# Adafruit_nRF52_Bluefruit_Feather_rev_G.net
KiCad netlist of a schematic drawn in EAGLE
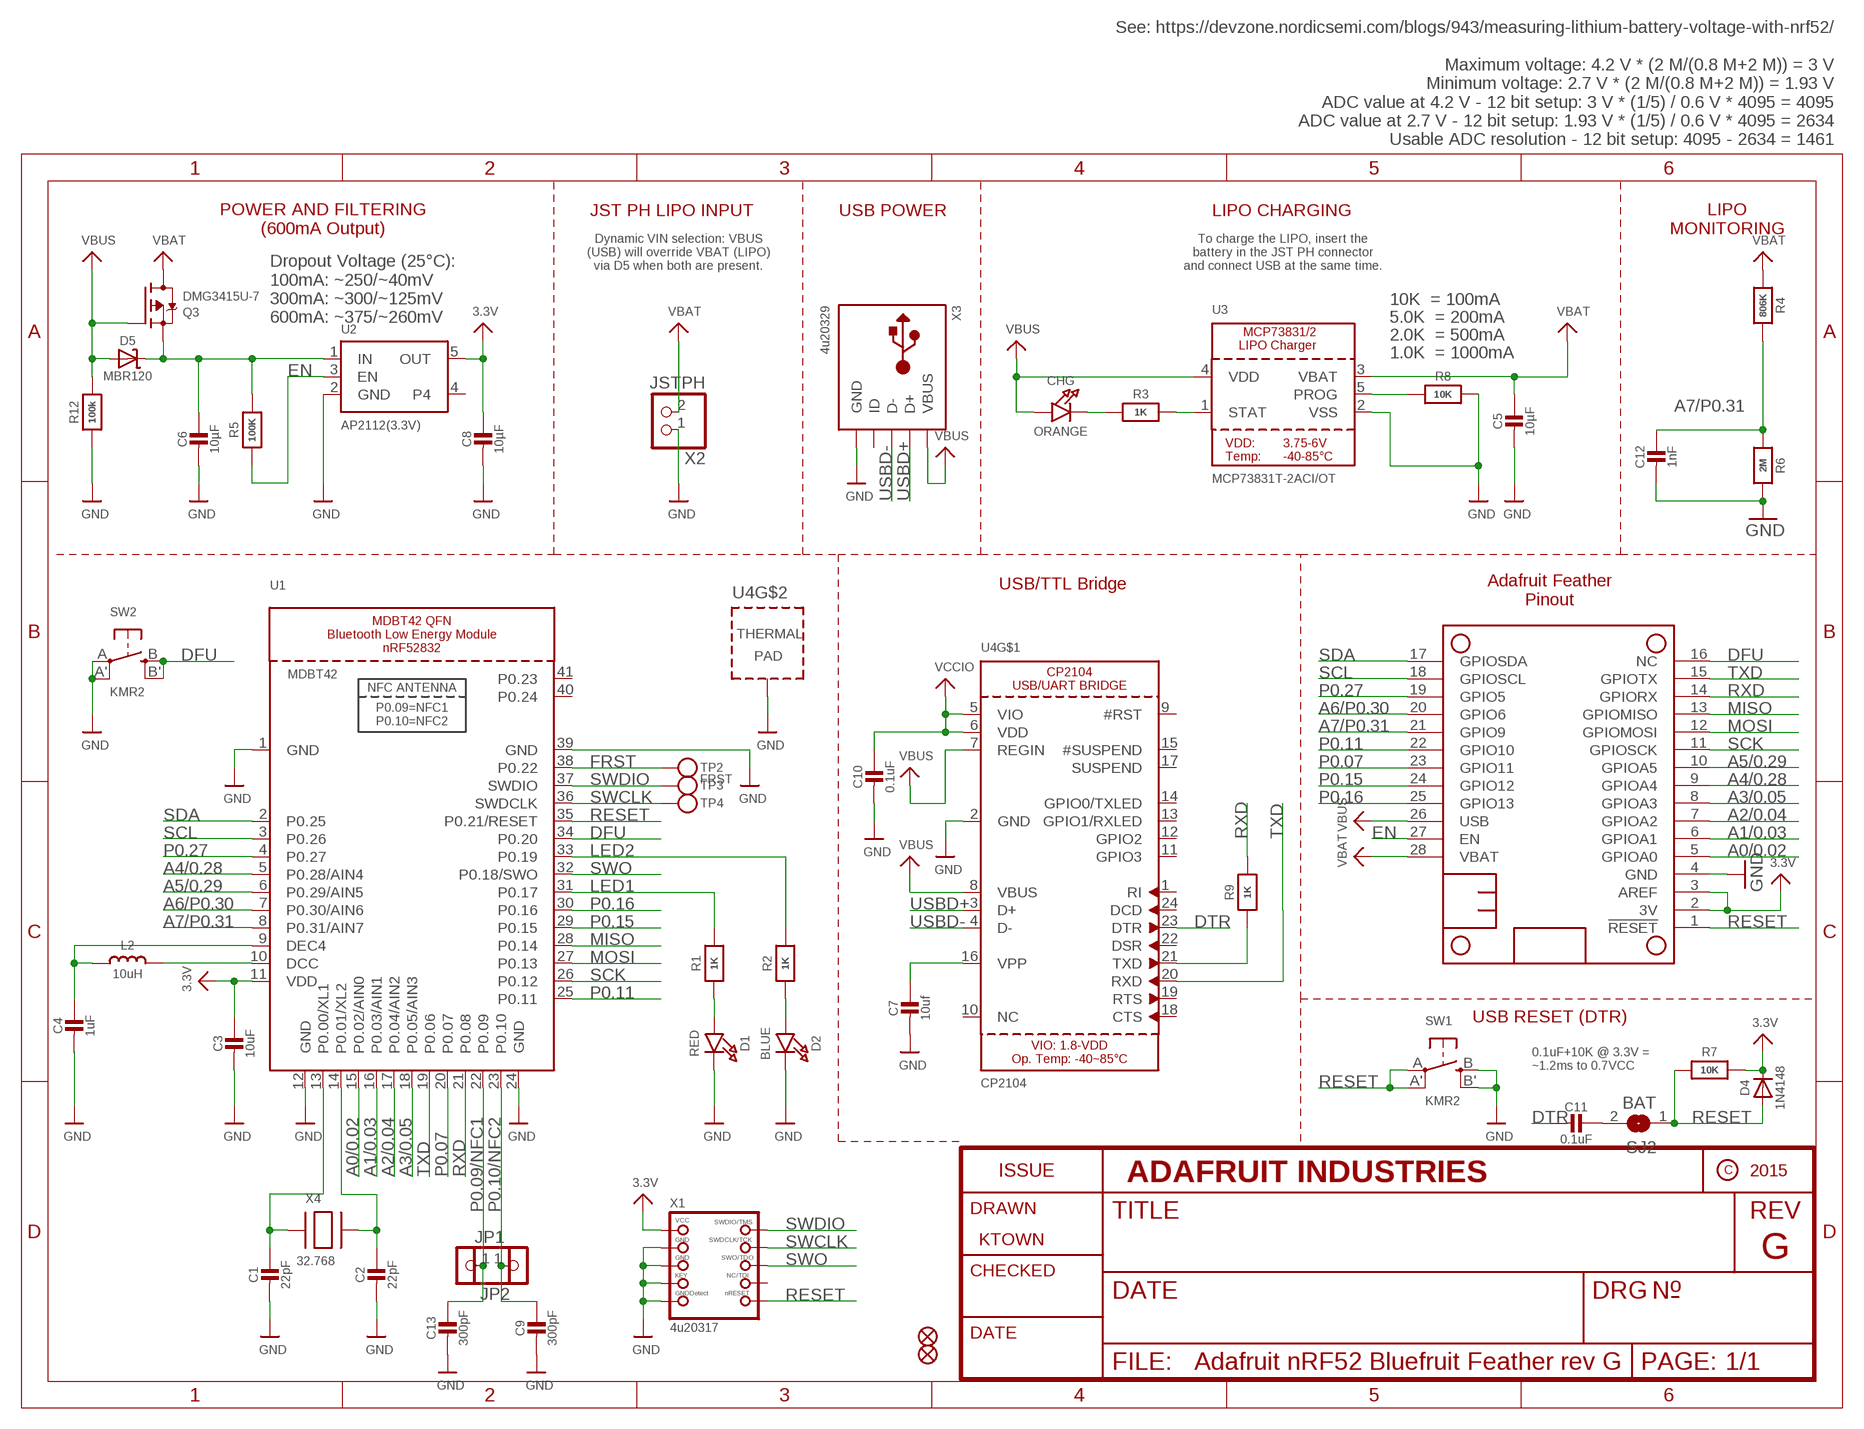
[diagram p0: schematic, sheet 1]

(export (version "E")
  (design (tool "Eeschema 10.0.6"))
  (components
    (comp (ref "C1")
      (value "22pF")
      (footprint "eagle-import:0603-NO")
      (libsource (lib "eagle-import") (part "CAP_CERAMIC0603_NO"))
    )
    (comp (ref "C2")
      (value "22pF")
      (footprint "eagle-import:0603-NO")
      (libsource (lib "eagle-import") (part "CAP_CERAMIC0603_NO"))
    )
    (comp (ref "C3")
      (value "10uF")
      (footprint "eagle-import:0805-NO")
      (libsource (lib "eagle-import") (part "CAP_CERAMIC0805-NOOUTLINE"))
    )
    (comp (ref "C4")
      (value "1uF")
      (footprint "eagle-import:0603-NO")
      (libsource (lib "eagle-import") (part "CAP_CERAMIC0603_NO"))
    )
    (comp (ref "C5")
      (value "10µF")
      (footprint "eagle-import:0805-NO")
      (libsource (lib "eagle-import") (part "CAP_CERAMIC0805-NOOUTLINE"))
    )
    (comp (ref "C6")
      (value "10µF")
      (footprint "eagle-import:0805-NO")
      (libsource (lib "eagle-import") (part "CAP_CERAMIC0805-NOOUTLINE"))
    )
    (comp (ref "C7")
      (value "10uf")
      (footprint "eagle-import:0805-NO")
      (libsource (lib "eagle-import") (part "CAP_CERAMIC0805-NOOUTLINE"))
    )
    (comp (ref "C8")
      (value "10µF")
      (footprint "eagle-import:0805-NO")
      (libsource (lib "eagle-import") (part "CAP_CERAMIC0805-NOOUTLINE"))
    )
    (comp (ref "C9")
      (value "300pF")
      (footprint "eagle-import:_0603MP")
      (libsource (lib "eagle-import") (part "CAP_CERAMIC_0603MP"))
    )
    (comp (ref "C10")
      (value "0.1uF")
      (footprint "eagle-import:0603-NO")
      (libsource (lib "eagle-import") (part "CAP_CERAMIC0603_NO"))
    )
    (comp (ref "C11")
      (value "0.1uF")
      (footprint "eagle-import:0603-NO")
      (libsource (lib "eagle-import") (part "CAP_CERAMIC0603_NO"))
    )
    (comp (ref "C12")
      (value "1nF")
      (footprint "eagle-import:0603-NO")
      (libsource (lib "eagle-import") (part "CAP_CERAMIC0603_NO"))
    )
    (comp (ref "C13")
      (value "300pF")
      (footprint "eagle-import:_0603MP")
      (libsource (lib "eagle-import") (part "CAP_CERAMIC_0603MP"))
    )
    (comp (ref "CHG")
      (value "ORANGE")
      (footprint "eagle-import:CHIPLED_0805_NOOUTLINE")
      (libsource (lib "eagle-import") (part "LED0805_NOOUTLINE"))
    )
    (comp (ref "D1")
      (value "RED")
      (footprint "eagle-import:CHIPLED_0805_NOOUTLINE")
      (libsource (lib "eagle-import") (part "LED0805_NOOUTLINE"))
    )
    (comp (ref "D2")
      (value "BLUE")
      (footprint "eagle-import:CHIPLED_0805_NOOUTLINE")
      (libsource (lib "eagle-import") (part "LED0805_NOOUTLINE"))
    )
    (comp (ref "D4")
      (value "1N4148")
      (footprint "eagle-import:SOD-323")
      (libsource (lib "eagle-import") (part "DIODESOD-323"))
    )
    (comp (ref "D5")
      (value "MBR120")
      (footprint "eagle-import:SOD-123")
      (libsource (lib "eagle-import") (part "DIODE-SCHOTTKYSOD-123"))
    )
    (comp (ref "FID1")
      (value "FIDUCIAL_1MM")
      (footprint "eagle-import:FIDUCIAL_1MM")
      (libsource (lib "eagle-import") (part "FIDUCIAL_1MM"))
    )
    (comp (ref "FID3")
      (value "FIDUCIAL_1MM")
      (footprint "eagle-import:FIDUCIAL_1MM")
      (libsource (lib "eagle-import") (part "FIDUCIAL_1MM"))
    )
    (comp (ref "JP1")
      (value "HEADER-1X12MM")
      (footprint "eagle-import:1X01_2MM")
      (libsource (lib "eagle-import") (part "HEADER-1X12MM"))
    )
    (comp (ref "JP2")
      (value "HEADER-1X12MM")
      (footprint "eagle-import:1X01_2MM")
      (libsource (lib "eagle-import") (part "HEADER-1X12MM"))
    )
    (comp (ref "L2")
      (value "10uH")
      (footprint "eagle-import:0805-NO")
      (libsource (lib "eagle-import") (part "INDUCTOR0805-NO"))
    )
    (comp (ref "MS1")
      (value "FEATHERWING_NODIM")
      (footprint "eagle-import:FEATHERWING_NODIM")
      (libsource (lib "eagle-import") (part "FEATHERWING_NODIM"))
    )
    (comp (ref "Q3")
      (value "DMG3415U-7")
      (footprint "eagle-import:SOT23-R")
      (libsource (lib "eagle-import") (part "MOSFET-P"))
    )
    (comp (ref "R1")
      (value "1K")
      (footprint "eagle-import:0603-NO")
      (libsource (lib "eagle-import") (part "RESISTOR_0603_NOOUT"))
    )
    (comp (ref "R2")
      (value "1K")
      (footprint "eagle-import:0603-NO")
      (libsource (lib "eagle-import") (part "RESISTOR_0603_NOOUT"))
    )
    (comp (ref "R3")
      (value "1K")
      (footprint "eagle-import:0603-NO")
      (libsource (lib "eagle-import") (part "RESISTOR_0603_NOOUT"))
    )
    (comp (ref "R4")
      (value "806K")
      (footprint "eagle-import:0603-NO")
      (libsource (lib "eagle-import") (part "RESISTOR_0603_NOOUT"))
    )
    (comp (ref "R5")
      (value "100K")
      (footprint "eagle-import:0603-NO")
      (libsource (lib "eagle-import") (part "RESISTOR_0603_NOOUT"))
    )
    (comp (ref "R6")
      (value "2M")
      (footprint "eagle-import:0603-NO")
      (libsource (lib "eagle-import") (part "RESISTOR_0603_NOOUT"))
    )
    (comp (ref "R7")
      (value "10K")
      (footprint "eagle-import:0603-NO")
      (libsource (lib "eagle-import") (part "RESISTOR_0603_NOOUT"))
    )
    (comp (ref "R8")
      (value "10K")
      (footprint "eagle-import:0603-NO")
      (libsource (lib "eagle-import") (part "RESISTOR_0603_NOOUT"))
    )
    (comp (ref "R9")
      (value "1K")
      (footprint "eagle-import:0603-NO")
      (libsource (lib "eagle-import") (part "RESISTOR_0603_NOOUT"))
    )
    (comp (ref "R12")
      (value "100k")
      (footprint "eagle-import:0603-NO")
      (libsource (lib "eagle-import") (part "RESISTOR_0603_NOOUT"))
    )
    (comp (ref "SJ2")
      (value "BAT")
      (footprint "eagle-import:SOLDERJUMPER_CLOSEDWIRE")
      (libsource (lib "eagle-import") (part "SOLDERJUMPERCLOSED"))
    )
    (comp (ref "SW1")
      (value "KMR2")
      (footprint "eagle-import:BTN_KMR2_4.6X2.8")
      (libsource (lib "eagle-import") (part "SWITCH_TACT_SMT4.6X2.8"))
    )
    (comp (ref "SW2")
      (value "KMR2")
      (footprint "eagle-import:BTN_KMR2_4.6X2.8")
      (libsource (lib "eagle-import") (part "SWITCH_TACT_SMT4.6X2.8"))
    )
    (comp (ref "TP2")
      (value "FRST")
      (footprint "eagle-import:PAD-1.5X2.0")
      (libsource (lib "eagle-import") (part "TESTPOINT1.5X2.0MM_NOCREAM"))
    )
    (comp (ref "TP3")
      (value "TESTPOINTROUND2MM")
      (footprint "eagle-import:TESTPOINT_ROUND_2MM")
      (libsource (lib "eagle-import") (part "TESTPOINTROUND2MM"))
    )
    (comp (ref "TP4")
      (value "TESTPOINTROUND2MM")
      (footprint "eagle-import:TESTPOINT_ROUND_2MM")
      (libsource (lib "eagle-import") (part "TESTPOINTROUND2MM"))
    )
    (comp (ref "U1")
      (value "MDBT42")
      (footprint "eagle-import:BLE_MODULE_RAYTAC_MDBT42")
      (libsource (lib "eagle-import") (part "NRF52832_MODULE_MDBT42"))
    )
    (comp (ref "U2")
      (value "AP2112(3.3V)")
      (footprint "eagle-import:SOT23-5")
      (libsource (lib "eagle-import") (part "VREG_SOT23-5"))
    )
    (comp (ref "U3")
      (value "MCP73831T-2ACI/OT")
      (footprint "eagle-import:SOT23-5")
      (libsource (lib "eagle-import") (part "MCP73831/2"))
    )
    (comp (ref "U4")
      (value "CP2104")
      (footprint "eagle-import:QFN24_4MM_SMSC")
      (libsource (lib "eagle-import") (part "CP2104"))
    )
    (comp (ref "X1")
      (value "4u20317")
      (footprint "eagle-import:2X05_1.27MM_BOX_POSTS")
      (libsource (lib "eagle-import") (part "JTAG-CORTEXBOXPOSTS"))
    )
    (comp (ref "X2")
      (value "JSTPH")
      (footprint "eagle-import:JSTPH2")
      (libsource (lib "eagle-import") (part "CON_JST_PH_2PIN"))
    )
    (comp (ref "X3")
      (value "4u20329")
      (footprint "eagle-import:4UCONN_20329_V2")
      (libsource (lib "eagle-import") (part "USB_MICRO_20329_V2"))
    )
    (comp (ref "X4")
      (value "32.768")
      (footprint "eagle-import:XTAL3215")
      (libsource (lib "eagle-import") (part "XTAL-3.2X1.5"))
    )
  )
  (nets
    (net (code "1") (name "/A0{slash}0.02") (class "Default")
      (node (ref "MS1") (pin "5") (pinfunction "GPIOA0_5") (pintype "bidirectional"))
      (node (ref "U1") (pin "15") (pinfunction "P0.02/AIN0_15") (pintype "bidirectional"))
    )
    (net (code "2") (name "/A1{slash}0.03") (class "Default")
      (node (ref "MS1") (pin "6") (pinfunction "GPIOA1_6") (pintype "bidirectional"))
      (node (ref "U1") (pin "16") (pinfunction "P0.03/AIN1_16") (pintype "bidirectional"))
    )
    (net (code "3") (name "/A2{slash}0.04") (class "Default")
      (node (ref "MS1") (pin "7") (pinfunction "GPIOA2_7") (pintype "bidirectional"))
      (node (ref "U1") (pin "17") (pinfunction "P0.04/AIN2_17") (pintype "bidirectional"))
    )
    (net (code "4") (name "/A3{slash}0.05") (class "Default")
      (node (ref "MS1") (pin "8") (pinfunction "GPIOA3_8") (pintype "bidirectional"))
      (node (ref "U1") (pin "18") (pinfunction "P0.05/AIN3_18") (pintype "bidirectional"))
    )
    (net (code "5") (name "/A4{slash}0.28") (class "Default")
      (node (ref "MS1") (pin "9") (pinfunction "GPIOA4_9") (pintype "bidirectional"))
      (node (ref "U1") (pin "5") (pinfunction "P0.28/AIN4_5") (pintype "bidirectional"))
    )
    (net (code "6") (name "/A5{slash}0.29") (class "Default")
      (node (ref "MS1") (pin "10") (pinfunction "GPIOA5_10") (pintype "bidirectional"))
      (node (ref "U1") (pin "6") (pinfunction "P0.29/AIN5_6") (pintype "bidirectional"))
    )
    (net (code "7") (name "/A6{slash}P0.30") (class "Default")
      (node (ref "MS1") (pin "20") (pinfunction "GPIO6_20") (pintype "bidirectional"))
      (node (ref "U1") (pin "7") (pinfunction "P0.30/AIN6_7") (pintype "bidirectional"))
    )
    (net (code "8") (name "/A7{slash}P0.31") (class "Default")
      (node (ref "C12") (pin "1") (pinfunction "1_1") (pintype "passive"))
      (node (ref "MS1") (pin "21") (pinfunction "GPIO9_21") (pintype "bidirectional"))
      (node (ref "R4") (pin "2") (pinfunction "2_2") (pintype "passive"))
      (node (ref "R6") (pin "1") (pinfunction "1_1") (pintype "passive"))
      (node (ref "U1") (pin "8") (pinfunction "P0.31/AIN7_8") (pintype "bidirectional"))
    )
    (net (code "9") (name "/DFU") (class "Default")
      (node (ref "MS1") (pin "16") (pinfunction "NC_16") (pintype "passive"))
      (node (ref "SW2") (pin "B") (pinfunction "S_B") (pintype "passive"))
      (node (ref "SW2") (pin "B'") (pinfunction "S1_B'") (pintype "passive"))
      (node (ref "U1") (pin "34") (pinfunction "P0.20_34") (pintype "bidirectional"))
    )
    (net (code "10") (name "/DTR") (class "Default")
      (node (ref "C11") (pin "2") (pinfunction "2_2") (pintype "passive"))
      (node (ref "U4") (pin "23") (pinfunction "DTR_23") (pintype "output"))
    )
    (net (code "11") (name "/EN") (class "Default")
      (node (ref "MS1") (pin "27") (pinfunction "EN_27") (pintype "passive"))
      (node (ref "R5") (pin "1") (pinfunction "1_1") (pintype "passive"))
      (node (ref "U2") (pin "3") (pinfunction "EN_3") (pintype "input"))
    )
    (net (code "12") (name "/FRST") (class "Default")
      (node (ref "TP2") (pin "P$1") (pinfunction "P$1_P$1") (pintype "bidirectional"))
      (node (ref "U1") (pin "38") (pinfunction "P0.22_38") (pintype "bidirectional"))
    )
    (net (code "13") (name "/LED1") (class "Default")
      (node (ref "R1") (pin "2") (pinfunction "2_2") (pintype "passive"))
      (node (ref "U1") (pin "31") (pinfunction "P0.17_31") (pintype "bidirectional"))
    )
    (net (code "14") (name "/LED2") (class "Default")
      (node (ref "R2") (pin "2") (pinfunction "2_2") (pintype "passive"))
      (node (ref "U1") (pin "33") (pinfunction "P0.19_33") (pintype "bidirectional"))
    )
    (net (code "15") (name "/MISO") (class "Default")
      (node (ref "MS1") (pin "13") (pinfunction "GPIOMISO_13") (pintype "bidirectional"))
      (node (ref "U1") (pin "28") (pinfunction "P0.14_28") (pintype "bidirectional"))
    )
    (net (code "16") (name "/MOSI") (class "Default")
      (node (ref "MS1") (pin "12") (pinfunction "GPIOMOSI_12") (pintype "bidirectional"))
      (node (ref "U1") (pin "27") (pinfunction "P0.13_27") (pintype "bidirectional"))
    )
    (net (code "17") (name "/P0.07") (class "Default")
      (node (ref "MS1") (pin "23") (pinfunction "GPIO11_23") (pintype "bidirectional"))
      (node (ref "U1") (pin "20") (pinfunction "P0.07_20") (pintype "bidirectional"))
    )
    (net (code "18") (name "/P0.09{slash}NFC1") (class "Default")
      (node (ref "C13") (pin "1") (pinfunction "1_1") (pintype "passive"))
      (node (ref "JP2") (pin "1") (pinfunction "1_1") (pintype "passive"))
      (node (ref "U1") (pin "22") (pinfunction "P0.09_22") (pintype "bidirectional"))
    )
    (net (code "19") (name "/P0.10{slash}NFC2") (class "Default")
      (node (ref "C9") (pin "1") (pinfunction "1_1") (pintype "passive"))
      (node (ref "JP1") (pin "1") (pinfunction "1_1") (pintype "passive"))
      (node (ref "U1") (pin "23") (pinfunction "P0.10_23") (pintype "bidirectional"))
    )
    (net (code "20") (name "/P0.11") (class "Default")
      (node (ref "MS1") (pin "22") (pinfunction "GPIO10_22") (pintype "bidirectional"))
      (node (ref "U1") (pin "25") (pinfunction "P0.11_25") (pintype "bidirectional"))
    )
    (net (code "21") (name "/P0.15") (class "Default")
      (node (ref "MS1") (pin "24") (pinfunction "GPIO12_24") (pintype "bidirectional"))
      (node (ref "U1") (pin "29") (pinfunction "P0.15_29") (pintype "bidirectional"))
    )
    (net (code "22") (name "/P0.16") (class "Default")
      (node (ref "MS1") (pin "25") (pinfunction "GPIO13_25") (pintype "bidirectional"))
      (node (ref "U1") (pin "30") (pinfunction "P0.16_30") (pintype "bidirectional"))
    )
    (net (code "23") (name "/P0.27") (class "Default")
      (node (ref "MS1") (pin "19") (pinfunction "GPIO5_19") (pintype "bidirectional"))
      (node (ref "U1") (pin "4") (pinfunction "P0.27_4") (pintype "bidirectional"))
    )
    (net (code "24") (name "/RESET") (class "Default")
      (node (ref "D4") (pin "A") (pinfunction "A_A") (pintype "passive"))
      (node (ref "MS1") (pin "1") (pinfunction "~{RESET}_1") (pintype "input"))
      (node (ref "R7") (pin "1") (pinfunction "1_1") (pintype "passive"))
      (node (ref "SJ2") (pin "1") (pinfunction "1_1") (pintype "passive"))
      (node (ref "SW1") (pin "A") (pinfunction "P_A") (pintype "passive"))
      (node (ref "SW1") (pin "A'") (pinfunction "P1_A'") (pintype "passive"))
      (node (ref "U1") (pin "35") (pinfunction "P0.21/RESET_35") (pintype "bidirectional"))
      (node (ref "X1") (pin "10") (pinfunction "NRESET_10") (pintype "bidirectional"))
    )
    (net (code "25") (name "/RXD") (class "Default")
      (node (ref "MS1") (pin "14") (pinfunction "GPIORX_14") (pintype "bidirectional"))
      (node (ref "R9") (pin "2") (pinfunction "2_2") (pintype "passive"))
      (node (ref "U1") (pin "21") (pinfunction "P0.08_21") (pintype "bidirectional"))
    )
    (net (code "26") (name "/SCK") (class "Default")
      (node (ref "MS1") (pin "11") (pinfunction "GPIOSCK_11") (pintype "bidirectional"))
      (node (ref "U1") (pin "26") (pinfunction "P0.12_26") (pintype "bidirectional"))
    )
    (net (code "27") (name "/SCL") (class "Default")
      (node (ref "MS1") (pin "18") (pinfunction "GPIOSCL_18") (pintype "bidirectional"))
      (node (ref "U1") (pin "3") (pinfunction "P0.26_3") (pintype "bidirectional"))
    )
    (net (code "28") (name "/SDA") (class "Default")
      (node (ref "MS1") (pin "17") (pinfunction "GPIOSDA_17") (pintype "bidirectional"))
      (node (ref "U1") (pin "2") (pinfunction "P0.25_2") (pintype "bidirectional"))
    )
    (net (code "29") (name "/SWCLK") (class "Default")
      (node (ref "TP4") (pin "P$1") (pinfunction "P$1_P$1") (pintype "bidirectional"))
      (node (ref "U1") (pin "36") (pinfunction "SWDCLK_36") (pintype "bidirectional"))
      (node (ref "X1") (pin "4") (pinfunction "SWDCLK_4") (pintype "bidirectional"))
    )
    (net (code "30") (name "/SWDIO") (class "Default")
      (node (ref "TP3") (pin "P$1") (pinfunction "P$1_P$1") (pintype "bidirectional"))
      (node (ref "U1") (pin "37") (pinfunction "SWDIO_37") (pintype "bidirectional"))
      (node (ref "X1") (pin "2") (pinfunction "SWDIO_2") (pintype "bidirectional"))
    )
    (net (code "31") (name "/SWO") (class "Default")
      (node (ref "U1") (pin "32") (pinfunction "P0.18/SWO_32") (pintype "bidirectional"))
      (node (ref "X1") (pin "6") (pinfunction "SWO_6") (pintype "bidirectional"))
    )
    (net (code "32") (name "/TXD") (class "Default")
      (node (ref "MS1") (pin "15") (pinfunction "GPIOTX_15") (pintype "bidirectional"))
      (node (ref "U1") (pin "19") (pinfunction "P0.06_19") (pintype "bidirectional"))
      (node (ref "U4") (pin "20") (pinfunction "RXD_20") (pintype "input"))
    )
    (net (code "33") (name "/USBD+") (class "Default")
      (node (ref "U4") (pin "3") (pinfunction "D+_3") (pintype "bidirectional"))
      (node (ref "X3") (pin "D+") (pinfunction "D+_D+") (pintype "bidirectional"))
    )
    (net (code "34") (name "/USBD-") (class "Default")
      (node (ref "U4") (pin "4") (pinfunction "D-_4") (pintype "bidirectional"))
      (node (ref "X3") (pin "D-") (pinfunction "D-_D-") (pintype "bidirectional"))
    )
    (net (code "35") (name "3.3V") (class "Default")
      (node (ref "C3") (pin "1") (pinfunction "1_1") (pintype "passive"))
      (node (ref "C8") (pin "1") (pinfunction "1_1") (pintype "passive"))
      (node (ref "D4") (pin "C") (pinfunction "C_C") (pintype "passive"))
      (node (ref "MS1") (pin "2") (pinfunction "3V_2") (pintype "power_in"))
      (node (ref "MS1") (pin "3") (pinfunction "AREF_3") (pintype "passive"))
      (node (ref "R7") (pin "2") (pinfunction "2_2") (pintype "passive"))
      (node (ref "U1") (pin "11") (pinfunction "VDD_11") (pintype "bidirectional"))
      (node (ref "U2") (pin "5") (pinfunction "OUT_5") (pintype "power_in"))
      (node (ref "X1") (pin "1") (pinfunction "VCC_1") (pintype "power_in"))
    )
    (net (code "36") (name "GND") (class "Default")
      (node (ref "C1") (pin "2") (pinfunction "2_2") (pintype "passive"))
      (node (ref "C10") (pin "2") (pinfunction "2_2") (pintype "passive"))
      (node (ref "C12") (pin "2") (pinfunction "2_2") (pintype "passive"))
      (node (ref "C13") (pin "2") (pinfunction "2_2") (pintype "passive"))
      (node (ref "C2") (pin "2") (pinfunction "2_2") (pintype "passive"))
      (node (ref "C3") (pin "2") (pinfunction "2_2") (pintype "passive"))
      (node (ref "C4") (pin "2") (pinfunction "2_2") (pintype "passive"))
      (node (ref "C5") (pin "2") (pinfunction "2_2") (pintype "passive"))
      (node (ref "C6") (pin "2") (pinfunction "2_2") (pintype "passive"))
      (node (ref "C7") (pin "2") (pinfunction "2_2") (pintype "passive"))
      (node (ref "C8") (pin "2") (pinfunction "2_2") (pintype "passive"))
      (node (ref "C9") (pin "2") (pinfunction "2_2") (pintype "passive"))
      (node (ref "D1") (pin "C") (pinfunction "C_C") (pintype "passive"))
      (node (ref "D2") (pin "C") (pinfunction "C_C") (pintype "passive"))
      (node (ref "MS1") (pin "4") (pinfunction "GND_4") (pintype "power_in"))
      (node (ref "R12") (pin "1") (pinfunction "1_1") (pintype "passive"))
      (node (ref "R6") (pin "2") (pinfunction "2_2") (pintype "passive"))
      (node (ref "R8") (pin "2") (pinfunction "2_2") (pintype "passive"))
      (node (ref "SW1") (pin "B") (pinfunction "S_B") (pintype "passive"))
      (node (ref "SW1") (pin "B'") (pinfunction "S1_B'") (pintype "passive"))
      (node (ref "SW2") (pin "A") (pinfunction "P_A") (pintype "passive"))
      (node (ref "SW2") (pin "A'") (pinfunction "P1_A'") (pintype "passive"))
      (node (ref "U1") (pin "1") (pinfunction "GND_1") (pintype "bidirectional"))
      (node (ref "U1") (pin "12") (pinfunction "GND_12") (pintype "bidirectional"))
      (node (ref "U1") (pin "24") (pinfunction "GND_24") (pintype "bidirectional"))
      (node (ref "U1") (pin "39") (pinfunction "GND_39") (pintype "bidirectional"))
      (node (ref "U2") (pin "2") (pinfunction "GND_2") (pintype "power_in"))
      (node (ref "U3") (pin "2") (pinfunction "VSS_2") (pintype "power_in"))
      (node (ref "U4") (pin "2") (pinfunction "GND_2") (pintype "power_in"))
      (node (ref "U4") (pin "THERM") (pinfunction "TP_THERM") (pintype "power_in"))
      (node (ref "X1") (pin "3") (pinfunction "GND_3") (pintype "power_in"))
      (node (ref "X1") (pin "5") (pinfunction "GND_5") (pintype "power_in"))
      (node (ref "X1") (pin "7") (pinfunction "KEY_7") (pintype "bidirectional"))
      (node (ref "X1") (pin "9") (pinfunction "GNDDETECT_9") (pintype "bidirectional"))
      (node (ref "X2") (pin "1") (pinfunction "1_1") (pintype "passive"))
      (node (ref "X3") (pin "BASE@1") (pinfunction "GND_BASE@1") (pintype "power_in"))
      (node (ref "X3") (pin "BASE@2") (pinfunction "GND_BASE@2") (pintype "power_in"))
      (node (ref "X3") (pin "GND") (pinfunction "GND_GND") (pintype "power_in"))
      (node (ref "X3") (pin "SPRT@1") (pinfunction "GND_SPRT@1") (pintype "power_in"))
      (node (ref "X3") (pin "SPRT@2") (pinfunction "GND_SPRT@2") (pintype "power_in"))
      (node (ref "X3") (pin "SPRT@3") (pinfunction "GND_SPRT@3") (pintype "power_in"))
      (node (ref "X3") (pin "SPRT@4") (pinfunction "GND_SPRT@4") (pintype "power_in"))
    )
    (net (code "37") (name "Net-(C11-Pad1)") (class "Default")
      (node (ref "C11") (pin "1") (pinfunction "1_1") (pintype "passive"))
      (node (ref "SJ2") (pin "2") (pinfunction "2_2") (pintype "passive"))
    )
    (net (code "38") (name "Net-(CHG-PadC)") (class "Default")
      (node (ref "CHG") (pin "C") (pinfunction "C_C") (pintype "passive"))
      (node (ref "R3") (pin "1") (pinfunction "1_1") (pintype "passive"))
    )
    (net (code "39") (name "Net-(D1-PadA)") (class "Default")
      (node (ref "D1") (pin "A") (pinfunction "A_A") (pintype "passive"))
      (node (ref "R1") (pin "1") (pinfunction "1_1") (pintype "passive"))
    )
    (net (code "40") (name "Net-(D2-PadA)") (class "Default")
      (node (ref "D2") (pin "A") (pinfunction "A_A") (pintype "passive"))
      (node (ref "R2") (pin "1") (pinfunction "1_1") (pintype "passive"))
    )
    (net (code "41") (name "Net-(Q3-S)") (class "Default")
      (node (ref "C6") (pin "1") (pinfunction "1_1") (pintype "passive"))
      (node (ref "D5") (pin "C") (pinfunction "C_C") (pintype "passive"))
      (node (ref "Q3") (pin "2") (pinfunction "S_2") (pintype "passive"))
      (node (ref "R5") (pin "2") (pinfunction "2_2") (pintype "passive"))
      (node (ref "U2") (pin "1") (pinfunction "IN_1") (pintype "power_in"))
    )
    (net (code "42") (name "Net-(U1-DCC)") (class "Default")
      (node (ref "L2") (pin "2") (pinfunction "2_2") (pintype "passive"))
      (node (ref "U1") (pin "10") (pinfunction "DCC_10") (pintype "bidirectional"))
    )
    (net (code "43") (name "Net-(U1-DEC4)") (class "Default")
      (node (ref "C4") (pin "1") (pinfunction "1_1") (pintype "passive"))
      (node (ref "L2") (pin "1") (pinfunction "1_1") (pintype "passive"))
      (node (ref "U1") (pin "9") (pinfunction "DEC4_9") (pintype "bidirectional"))
    )
    (net (code "44") (name "Net-(U1-P0.00{slash}XL1)") (class "Default")
      (node (ref "C1") (pin "1") (pinfunction "1_1") (pintype "passive"))
      (node (ref "U1") (pin "13") (pinfunction "P0.00/XL1_13") (pintype "bidirectional"))
      (node (ref "X4") (pin "P$1") (pinfunction "P$1_P$1") (pintype "bidirectional"))
    )
    (net (code "45") (name "Net-(U1-P0.01{slash}XL2)") (class "Default")
      (node (ref "C2") (pin "1") (pinfunction "1_1") (pintype "passive"))
      (node (ref "U1") (pin "14") (pinfunction "P0.01/XL2_14") (pintype "bidirectional"))
      (node (ref "X4") (pin "P$2") (pinfunction "P$2_P$2") (pintype "bidirectional"))
    )
    (net (code "46") (name "Net-(U3-PROG)") (class "Default")
      (node (ref "R8") (pin "1") (pinfunction "1_1") (pintype "passive"))
      (node (ref "U3") (pin "5") (pinfunction "PROG_5") (pintype "input"))
    )
    (net (code "47") (name "Net-(U3-STAT)") (class "Default")
      (node (ref "R3") (pin "2") (pinfunction "2_2") (pintype "passive"))
      (node (ref "U3") (pin "1") (pinfunction "STAT_1") (pintype "output"))
    )
    (net (code "48") (name "Net-(U4A-TXD)") (class "Default")
      (node (ref "R9") (pin "1") (pinfunction "1_1") (pintype "passive"))
      (node (ref "U4") (pin "21") (pinfunction "TXD_21") (pintype "output"))
    )
    (net (code "49") (name "Net-(U4A-VPP)") (class "Default")
      (node (ref "C7") (pin "1") (pinfunction "1_1") (pintype "passive"))
      (node (ref "U4") (pin "16") (pinfunction "VPP_16") (pintype "bidirectional"))
    )
    (net (code "50") (name "VBAT") (class "Default")
      (node (ref "C5") (pin "1") (pinfunction "1_1") (pintype "passive"))
      (node (ref "MS1") (pin "28") (pinfunction "VBAT_28") (pintype "power_in"))
      (node (ref "Q3") (pin "3") (pinfunction "D_3") (pintype "passive"))
      (node (ref "R4") (pin "1") (pinfunction "1_1") (pintype "passive"))
      (node (ref "U3") (pin "3") (pinfunction "VBAT_3") (pintype "power_in"))
      (node (ref "X2") (pin "2") (pinfunction "2_2") (pintype "passive"))
    )
    (net (code "51") (name "VBUS") (class "Default")
      (node (ref "CHG") (pin "A") (pinfunction "A_A") (pintype "passive"))
      (node (ref "D5") (pin "A") (pinfunction "A_A") (pintype "passive"))
      (node (ref "MS1") (pin "26") (pinfunction "USB_26") (pintype "power_in"))
      (node (ref "Q3") (pin "1") (pinfunction "G_1") (pintype "passive"))
      (node (ref "R12") (pin "2") (pinfunction "2_2") (pintype "passive"))
      (node (ref "U3") (pin "4") (pinfunction "VDD_4") (pintype "power_in"))
      (node (ref "U4") (pin "7") (pinfunction "REGIN_7") (pintype "power_in"))
      (node (ref "U4") (pin "8") (pinfunction "VBUS_8") (pintype "power_in"))
      (node (ref "X3") (pin "VBUS") (pinfunction "VBUS_VBUS") (pintype "power_in"))
    )
    (net (code "52") (name "VCCIO") (class "Default")
      (node (ref "C10") (pin "1") (pinfunction "1_1") (pintype "passive"))
      (node (ref "U4") (pin "5") (pinfunction "VIO_5") (pintype "power_in"))
      (node (ref "U4") (pin "6") (pinfunction "VDD_6") (pintype "power_in"))
    )
    (net (code "53") (name "unconnected-(U1-P0.23-Pad41)") (class "Default")
      (node (ref "U1") (pin "41") (pinfunction "P0.23_41") (pintype "bidirectional"))
    )
    (net (code "54") (name "unconnected-(U1-P0.24-Pad40)") (class "Default")
      (node (ref "U1") (pin "40") (pinfunction "P0.24_40") (pintype "bidirectional"))
    )
    (net (code "55") (name "unconnected-(U2-P4-Pad4)") (class "Default")
      (node (ref "U2") (pin "4") (pinfunction "P4_4") (pintype "bidirectional"))
    )
    (net (code "56") (name "unconnected-(U4A-#RST-Pad9)") (class "Default")
      (node (ref "U4") (pin "9") (pinfunction "#RST_9") (pintype "bidirectional"))
    )
    (net (code "57") (name "unconnected-(U4A-#SUSPEND-Pad15)") (class "Default")
      (node (ref "U4") (pin "15") (pinfunction "#SUSPEND_15") (pintype "output"))
    )
    (net (code "58") (name "unconnected-(U4A-CTS-Pad18)") (class "Default")
      (node (ref "U4") (pin "18") (pinfunction "CTS_18") (pintype "input"))
    )
    (net (code "59") (name "unconnected-(U4A-DCD-Pad24)") (class "Default")
      (node (ref "U4") (pin "24") (pinfunction "DCD_24") (pintype "input"))
    )
    (net (code "60") (name "unconnected-(U4A-DSR-Pad22)") (class "Default")
      (node (ref "U4") (pin "22") (pinfunction "DSR_22") (pintype "input"))
    )
    (net (code "61") (name "unconnected-(U4A-GPIO0{slash}TXLED-Pad14)") (class "Default")
      (node (ref "U4") (pin "14") (pinfunction "GPIO0/TXLED_14") (pintype "bidirectional"))
    )
    (net (code "62") (name "unconnected-(U4A-GPIO1{slash}RXLED-Pad13)") (class "Default")
      (node (ref "U4") (pin "13") (pinfunction "GPIO1/RXLED_13") (pintype "bidirectional"))
    )
    (net (code "63") (name "unconnected-(U4A-GPIO2-Pad12)") (class "Default")
      (node (ref "U4") (pin "12") (pinfunction "GPIO2_12") (pintype "bidirectional"))
    )
    (net (code "64") (name "unconnected-(U4A-GPIO3-Pad11)") (class "Default")
      (node (ref "U4") (pin "11") (pinfunction "GPIO3_11") (pintype "bidirectional"))
    )
    (net (code "65") (name "unconnected-(U4A-NC-Pad10)") (class "Default")
      (node (ref "U4") (pin "10") (pinfunction "NC_10") (pintype "no_connect"))
    )
    (net (code "66") (name "unconnected-(U4A-RI-Pad1)") (class "Default")
      (node (ref "U4") (pin "1") (pinfunction "RI_1") (pintype "input"))
    )
    (net (code "67") (name "unconnected-(U4A-RTS-Pad19)") (class "Default")
      (node (ref "U4") (pin "19") (pinfunction "RTS_19") (pintype "output"))
    )
    (net (code "68") (name "unconnected-(U4A-SUSPEND-Pad17)") (class "Default")
      (node (ref "U4") (pin "17") (pinfunction "SUSPEND_17") (pintype "output"))
    )
    (net (code "69") (name "unconnected-(X1-TDI-Pad8)") (class "Default")
      (node (ref "X1") (pin "8") (pinfunction "TDI_8") (pintype "bidirectional"))
    )
    (net (code "70") (name "unconnected-(X3-PadID)") (class "Default")
      (node (ref "X3") (pin "ID") (pinfunction "ID_ID") (pintype "bidirectional"))
    )
  )
)
